# 00_POWER.net
KiCad netlist of a schematic drawn in Altium Designer
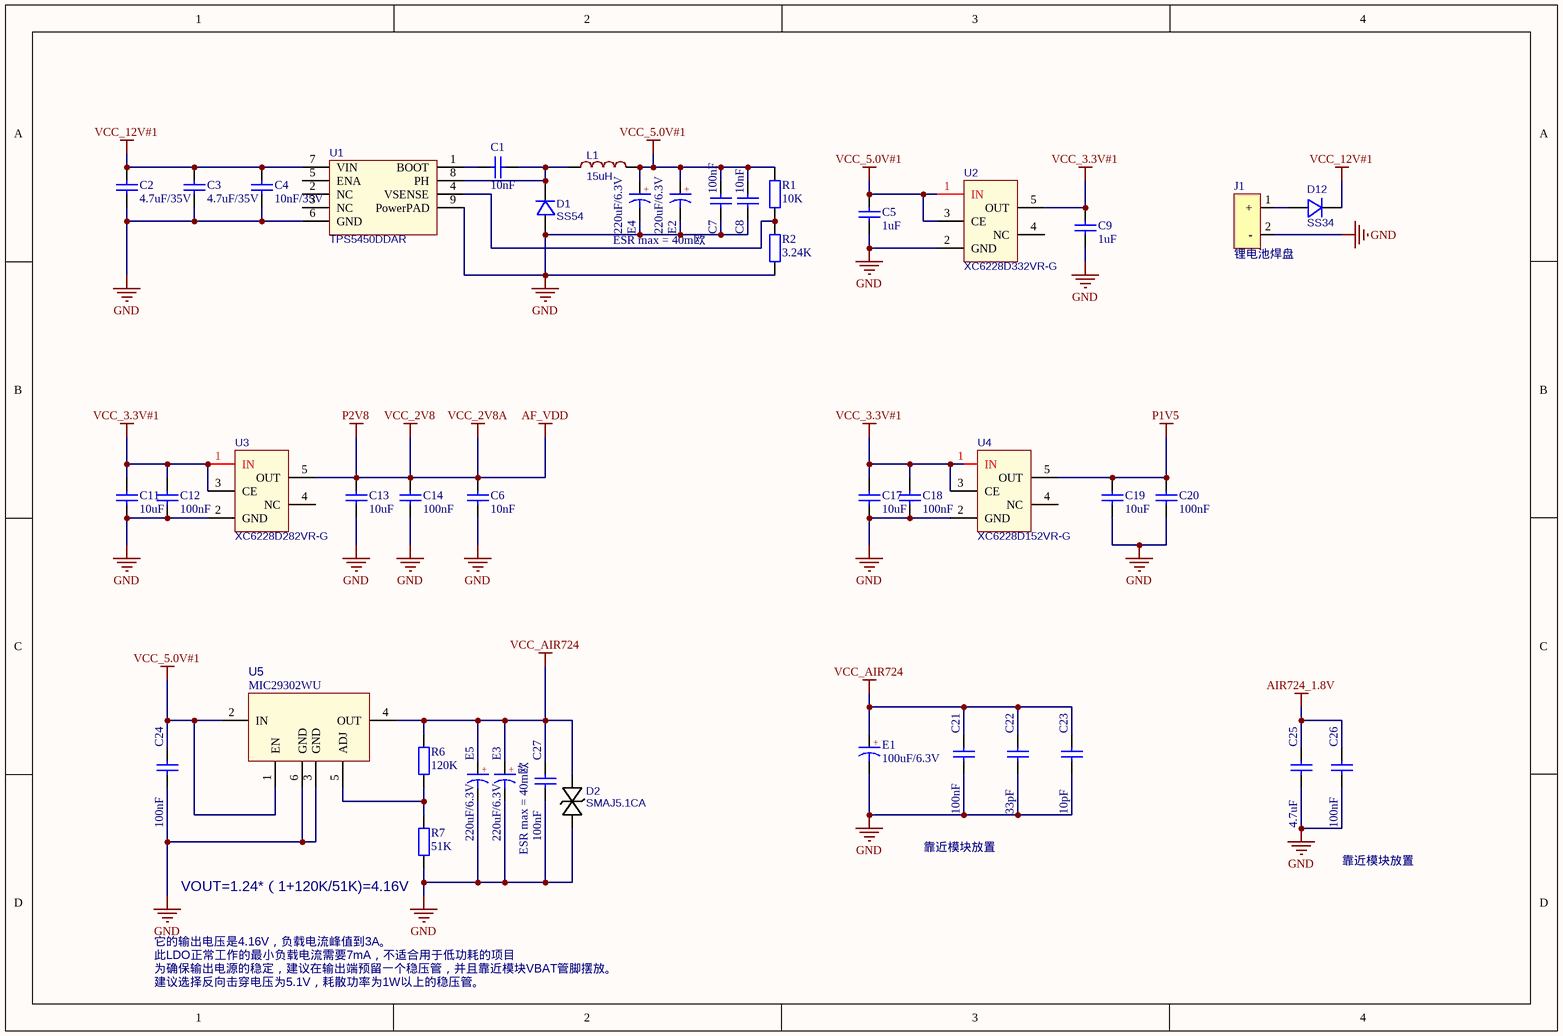
[diagram p0: 00_POWER.SchDoc]

(export (version "E")
  (design (tool "Eeschema 10.0.6"))
  (components
    (comp (ref "C1")
      (value "10nF")
      (footprint "0603-C")
      (description "贴片电容")
      (libsource (lib "封装库") (part "C"))
    )
    (comp (ref "C2")
      (value "4.7uF/35V")
      (footprint "0805-C")
      (description "贴片电容")
      (libsource (lib "封装库") (part "C"))
    )
    (comp (ref "C3")
      (value "4.7uF/35V")
      (footprint "0805-C")
      (description "贴片电容")
      (libsource (lib "封装库") (part "C"))
    )
    (comp (ref "C4")
      (value "10nF/35V")
      (footprint "0603-C")
      (description "贴片电容")
      (libsource (lib "封装库") (part "C"))
    )
    (comp (ref "C5")
      (value "1uF")
      (footprint "0603-C")
      (description "贴片电容")
      (libsource (lib "封装库") (part "C"))
    )
    (comp (ref "C6")
      (value "10nF")
      (footprint "0603-C")
      (description "贴片电容")
      (libsource (lib "封装库") (part "C"))
    )
    (comp (ref "C7")
      (value "100nF")
      (footprint "0603-C")
      (description "贴片电容")
      (libsource (lib "封装库") (part "C"))
    )
    (comp (ref "C8")
      (value "10nF")
      (footprint "0603-C")
      (description "贴片电容")
      (libsource (lib "封装库") (part "C"))
    )
    (comp (ref "C9")
      (value "1uF")
      (footprint "0603-C")
      (description "贴片电容")
      (libsource (lib "封装库") (part "C"))
    )
    (comp (ref "C11")
      (value "10uF")
      (footprint "0603-C")
      (description "贴片电容")
      (libsource (lib "封装库") (part "C"))
    )
    (comp (ref "C12")
      (value "100nF")
      (footprint "0603-C")
      (description "贴片电容")
      (libsource (lib "封装库") (part "C"))
    )
    (comp (ref "C13")
      (value "10uF")
      (footprint "0603-C")
      (description "贴片电容")
      (libsource (lib "封装库") (part "C"))
    )
    (comp (ref "C14")
      (value "100nF")
      (footprint "0603-C")
      (description "贴片电容")
      (libsource (lib "封装库") (part "C"))
    )
    (comp (ref "C17")
      (value "10uF")
      (footprint "0603-C")
      (description "贴片电容")
      (libsource (lib "封装库") (part "C"))
    )
    (comp (ref "C18")
      (value "100nF")
      (footprint "0603-C")
      (description "贴片电容")
      (libsource (lib "封装库") (part "C"))
    )
    (comp (ref "C19")
      (value "10uF")
      (footprint "0603-C")
      (description "贴片电容")
      (libsource (lib "封装库") (part "C"))
    )
    (comp (ref "C20")
      (value "100nF")
      (footprint "0603-C")
      (description "贴片电容")
      (libsource (lib "封装库") (part "C"))
    )
    (comp (ref "C21")
      (value "100nF")
      (footprint "0603-C")
      (description "贴片电容")
      (libsource (lib "封装库") (part "C"))
    )
    (comp (ref "C22")
      (value "33pF")
      (footprint "0603-C")
      (description "贴片电容")
      (libsource (lib "封装库") (part "C"))
    )
    (comp (ref "C23")
      (value "10pF")
      (footprint "0603-C")
      (description "贴片电容")
      (libsource (lib "封装库") (part "C"))
    )
    (comp (ref "C24")
      (value "100nF")
      (footprint "0603-C")
      (description "贴片电容")
      (libsource (lib "封装库") (part "C"))
    )
    (comp (ref "C25")
      (value "4.7uF")
      (footprint "0603-C")
      (description "贴片电容")
      (libsource (lib "封装库") (part "C"))
    )
    (comp (ref "C26")
      (value "100nF")
      (footprint "0603-C")
      (description "贴片电容")
      (libsource (lib "封装库") (part "C"))
    )
    (comp (ref "C27")
      (value "100nF")
      (footprint "0603-C")
      (description "贴片电容")
      (libsource (lib "封装库") (part "C"))
    )
    (comp (ref "D1")
      (value "SS54")
      (footprint "SS34-SMA")
      (fields
        (field (name "BOM_SUPPLIER PART") "C118334")
        (field (name "BOM_MANUFACTURER PART") "D-G060306G1-KS2")
        (field (name "CONTRIBUTOR") "LCSC")
      )
      (libsource (lib "封装库") (part "SS34"))
    )
    (comp (ref "D2")
      (value "SMAJ5.1CA")
      (footprint "ZENER")
      (description "SMAJ6.0CA_C698928")
      (fields
        (field (name "BOM_SUPPLIER PART") "C698928")
        (field (name "BOM_MANUFACTURER PART") "SMAJ6.0CA")
        (field (name "CONTRIBUTOR") "LCSC")
      )
      (libsource (lib "封装库") (part "SMAJ6.0CA"))
    )
    (comp (ref "D12")
      (value "SS34")
      (footprint "SS34-SMA")
      (fields
        (field (name "BOM_SUPPLIER PART") "C118334")
        (field (name "BOM_MANUFACTURER PART") "D-G060306G1-KS2")
        (field (name "CONTRIBUTOR") "LCSC")
      )
      (libsource (lib "封装库") (part "SS34"))
    )
    (comp (ref "E1")
      (value "100uF/6.3V")
      (footprint "CD B(3528)")
      (description "贴片钽电容")
      (libsource (lib "封装库") (part "CT"))
    )
    (comp (ref "E2")
      (value "220uF/6.3V")
      (footprint "CD B(3528)")
      (description "贴片钽电容")
      (libsource (lib "封装库") (part "CT"))
    )
    (comp (ref "E3")
      (value "220uF/6.3V")
      (footprint "CD B(3528)")
      (description "贴片钽电容")
      (libsource (lib "封装库") (part "CT"))
    )
    (comp (ref "E4")
      (value "220uF/6.3V")
      (footprint "CD B(3528)")
      (description "贴片钽电容")
      (libsource (lib "封装库") (part "CT"))
    )
    (comp (ref "E5")
      (value "220uF/6.3V")
      (footprint "CD B(3528)")
      (description "贴片钽电容")
      (libsource (lib "封装库") (part "CT"))
    )
    (comp (ref "J1") (value "锂电池焊盘") (footprint "锂电池焊盘") (libsource (lib "封装库") (part "锂电池焊盘")))
    (comp (ref "L1")
      (value "15uH")
      (footprint "电感7*7*3")
      (description "L")
      (fields
        (field (name "BOM_MANUFACTURER PART") "UPZ2012D800-4R0TF")
        (field (name "BOM_SUPPLIER PART") "C145060")
        (field (name "CONTRIBUTOR") "LCSC")
      )
      (libsource (lib "封装库") (part "L"))
    )
    (comp (ref "R1")
      (value "10K")
      (footprint "0603-R")
      (description "贴片电阻")
      (libsource (lib "封装库") (part "R"))
    )
    (comp (ref "R2")
      (value "3.24K")
      (footprint "0603-R")
      (description "贴片电阻")
      (libsource (lib "封装库") (part "R"))
    )
    (comp (ref "R6")
      (value "120K")
      (footprint "0603-R")
      (description "贴片电阻")
      (libsource (lib "封装库") (part "R"))
    )
    (comp (ref "R7")
      (value "51K")
      (footprint "0603-R")
      (description "贴片电阻")
      (libsource (lib "封装库") (part "R"))
    )
    (comp (ref "U1")
      (value "TPS5450DDAR")
      (footprint "TPS5430")
      (fields (field (name "BOM_MANUFACTURER PART") "TPS5430DDAR") (field (name "BOM_SUPPLIER PART") "C9864"))
      (libsource (lib "封装库") (part "TPS5430DDAR"))
    )
    (comp (ref "U2")
      (value "XC6228D332VR-G")
      (footprint "XC6228D332VR-G")
      (fields (field (name "BOM_SUPPLIER PART") "C69841"))
      (libsource (lib "封装库") (part "XC6228D332VR-G"))
    )
    (comp (ref "U3")
      (value "XC6228D282VR-G")
      (footprint "XC6228D332VR-G")
      (fields
        (field (name "BOM_MANUFACTURER PART") "XC6228D332VR-G")
        (field (name "BOM_SUPPLIER PART") "C69841")
      )
      (libsource (lib "封装库") (part "XC6228D282VR-G"))
    )
    (comp (ref "U4")
      (value "XC6228D152VR-G")
      (footprint "XC6228D332VR-G")
      (fields
        (field (name "BOM_MANUFACTURER PART") "XC6228D332VR-G")
        (field (name "BOM_SUPPLIER PART") "C69841")
      )
      (libsource (lib "封装库") (part "XC6228D282VR-G"))
    )
    (comp (ref "U5")
      (value "MIC29302WU")
      (footprint "MIC29302WU")
      (fields (field (name "MANUFACTURER") "UMW(友台半导体)"))
      (libsource (lib "封装库") (part "MIC29302WU"))
    )
  )
  (nets
    (net (code "1") (name "AF_VDD") (class "Default")
      (node (ref "C13") (pin "2") (pinfunction "2_2") (pintype "passive"))
      (node (ref "C14") (pin "2") (pinfunction "2_2") (pintype "passive"))
      (node (ref "C6") (pin "2") (pinfunction "2_2") (pintype "passive"))
      (node (ref "U3") (pin "5") (pinfunction "OUT_5") (pintype "passive"))
    )
    (net (code "2") (name "AIR724_1.8V") (class "Default")
      (node (ref "C25") (pin "2") (pinfunction "2_2") (pintype "passive"))
      (node (ref "C26") (pin "2") (pinfunction "2_2") (pintype "passive"))
    )
    (net (code "3") (name "GND") (class "Default")
      (node (ref "C11") (pin "1") (pinfunction "1_1") (pintype "passive"))
      (node (ref "C12") (pin "1") (pinfunction "1_1") (pintype "passive"))
      (node (ref "C13") (pin "1") (pinfunction "1_1") (pintype "passive"))
      (node (ref "C14") (pin "1") (pinfunction "1_1") (pintype "passive"))
      (node (ref "C17") (pin "1") (pinfunction "1_1") (pintype "passive"))
      (node (ref "C18") (pin "1") (pinfunction "1_1") (pintype "passive"))
      (node (ref "C19") (pin "1") (pinfunction "1_1") (pintype "passive"))
      (node (ref "C2") (pin "2") (pinfunction "2_2") (pintype "passive"))
      (node (ref "C20") (pin "1") (pinfunction "1_1") (pintype "passive"))
      (node (ref "C21") (pin "1") (pinfunction "1_1") (pintype "passive"))
      (node (ref "C22") (pin "1") (pinfunction "1_1") (pintype "passive"))
      (node (ref "C23") (pin "1") (pinfunction "1_1") (pintype "passive"))
      (node (ref "C24") (pin "1") (pinfunction "1_1") (pintype "passive"))
      (node (ref "C25") (pin "1") (pinfunction "1_1") (pintype "passive"))
      (node (ref "C26") (pin "1") (pinfunction "1_1") (pintype "passive"))
      (node (ref "C27") (pin "1") (pinfunction "1_1") (pintype "passive"))
      (node (ref "C3") (pin "2") (pinfunction "2_2") (pintype "passive"))
      (node (ref "C4") (pin "1") (pinfunction "1_1") (pintype "passive"))
      (node (ref "C5") (pin "1") (pinfunction "1_1") (pintype "passive"))
      (node (ref "C6") (pin "1") (pinfunction "1_1") (pintype "passive"))
      (node (ref "C7") (pin "2") (pinfunction "2_2") (pintype "passive"))
      (node (ref "C8") (pin "2") (pinfunction "2_2") (pintype "passive"))
      (node (ref "C9") (pin "1") (pinfunction "1_1") (pintype "passive"))
      (node (ref "D1") (pin "1") (pinfunction "+_1") (pintype "passive"))
      (node (ref "D2") (pin "2") (pinfunction "A_2") (pintype "passive"))
      (node (ref "E1") (pin "2") (pinfunction "K_2") (pintype "passive"))
      (node (ref "E2") (pin "2") (pinfunction "K_2") (pintype "passive"))
      (node (ref "E3") (pin "2") (pinfunction "K_2") (pintype "passive"))
      (node (ref "E4") (pin "2") (pinfunction "K_2") (pintype "passive"))
      (node (ref "E5") (pin "2") (pinfunction "K_2") (pintype "passive"))
      (node (ref "J1") (pin "2") (pinfunction "-_2") (pintype "passive"))
      (node (ref "R2") (pin "2") (pinfunction "2_2") (pintype "passive"))
      (node (ref "R7") (pin "2") (pinfunction "2_2") (pintype "passive"))
      (node (ref "U1") (pin "6") (pinfunction "GND_6") (pintype "passive"))
      (node (ref "U1") (pin "9") (pinfunction "PowerPAD_9") (pintype "passive"))
      (node (ref "U2") (pin "2") (pinfunction "GND_2") (pintype "passive"))
      (node (ref "U3") (pin "2") (pinfunction "GND_2") (pintype "passive"))
      (node (ref "U4") (pin "2") (pinfunction "GND_2") (pintype "passive"))
      (node (ref "U5") (pin "3") (pinfunction "GND_3") (pintype "passive"))
      (node (ref "U5") (pin "6") (pinfunction "GND_6") (pintype "passive"))
    )
    (net (code "4") (name "Net-(D1--)") (class "Default")
      (node (ref "C1") (pin "1") (pinfunction "1_1") (pintype "passive"))
      (node (ref "D1") (pin "2") (pinfunction "-_2") (pintype "passive"))
      (node (ref "L1") (pin "1") (pinfunction "1_1") (pintype "passive"))
      (node (ref "U1") (pin "8") (pinfunction "PH_8") (pintype "passive"))
    )
    (net (code "5") (name "Net-(D12-+)") (class "Default")
      (node (ref "D12") (pin "1") (pinfunction "+_1") (pintype "passive"))
      (node (ref "J1") (pin "1") (pinfunction "+_1") (pintype "passive"))
    )
    (net (code "6") (name "Net-(U1-BOOT)") (class "Default")
      (node (ref "C1") (pin "2") (pinfunction "2_2") (pintype "passive"))
      (node (ref "U1") (pin "1") (pinfunction "BOOT_1") (pintype "passive"))
    )
    (net (code "7") (name "Net-(U1-VSENSE)") (class "Default")
      (node (ref "R1") (pin "2") (pinfunction "2_2") (pintype "passive"))
      (node (ref "R2") (pin "1") (pinfunction "1_1") (pintype "passive"))
      (node (ref "U1") (pin "4") (pinfunction "VSENSE_4") (pintype "passive"))
    )
    (net (code "8") (name "Net-(U5-ADJ)") (class "Default")
      (node (ref "R6") (pin "2") (pinfunction "2_2") (pintype "passive"))
      (node (ref "R7") (pin "1") (pinfunction "1_1") (pintype "passive"))
      (node (ref "U5") (pin "5") (pinfunction "ADJ_5") (pintype "passive"))
    )
    (net (code "9") (name "P1V5") (class "Default")
      (node (ref "C19") (pin "2") (pinfunction "2_2") (pintype "passive"))
      (node (ref "C20") (pin "2") (pinfunction "2_2") (pintype "passive"))
      (node (ref "U4") (pin "5") (pinfunction "OUT_5") (pintype "passive"))
    )
    (net (code "10") (name "VCC_3.3V#1") (class "Default")
      (node (ref "C11") (pin "2") (pinfunction "2_2") (pintype "passive"))
      (node (ref "C12") (pin "2") (pinfunction "2_2") (pintype "passive"))
      (node (ref "C17") (pin "2") (pinfunction "2_2") (pintype "passive"))
      (node (ref "C18") (pin "2") (pinfunction "2_2") (pintype "passive"))
      (node (ref "C9") (pin "2") (pinfunction "2_2") (pintype "passive"))
      (node (ref "U2") (pin "5") (pinfunction "OUT_5") (pintype "passive"))
      (node (ref "U3") (pin "1") (pinfunction "IN_1") (pintype "passive"))
      (node (ref "U3") (pin "3") (pinfunction "CE_3") (pintype "passive"))
      (node (ref "U4") (pin "1") (pinfunction "IN_1") (pintype "passive"))
      (node (ref "U4") (pin "3") (pinfunction "CE_3") (pintype "passive"))
    )
    (net (code "11") (name "VCC_5.0V#1") (class "Default")
      (node (ref "C24") (pin "2") (pinfunction "2_2") (pintype "passive"))
      (node (ref "C5") (pin "2") (pinfunction "2_2") (pintype "passive"))
      (node (ref "C7") (pin "1") (pinfunction "1_1") (pintype "passive"))
      (node (ref "C8") (pin "1") (pinfunction "1_1") (pintype "passive"))
      (node (ref "E2") (pin "1") (pinfunction "A_1") (pintype "passive"))
      (node (ref "E4") (pin "1") (pinfunction "A_1") (pintype "passive"))
      (node (ref "L1") (pin "2") (pinfunction "2_2") (pintype "passive"))
      (node (ref "R1") (pin "1") (pinfunction "1_1") (pintype "passive"))
      (node (ref "U2") (pin "1") (pinfunction "IN_1") (pintype "passive"))
      (node (ref "U2") (pin "3") (pinfunction "CE_3") (pintype "passive"))
      (node (ref "U5") (pin "1") (pinfunction "EN_1") (pintype "passive"))
      (node (ref "U5") (pin "2") (pinfunction "IN_2") (pintype "passive"))
    )
    (net (code "12") (name "VCC_12V#1") (class "Default")
      (node (ref "C2") (pin "1") (pinfunction "1_1") (pintype "passive"))
      (node (ref "C3") (pin "1") (pinfunction "1_1") (pintype "passive"))
      (node (ref "C4") (pin "2") (pinfunction "2_2") (pintype "passive"))
      (node (ref "D12") (pin "2") (pinfunction "-_2") (pintype "passive"))
      (node (ref "U1") (pin "7") (pinfunction "VIN_7") (pintype "passive"))
    )
    (net (code "13") (name "VCC_AIR724") (class "Default")
      (node (ref "C21") (pin "2") (pinfunction "2_2") (pintype "passive"))
      (node (ref "C22") (pin "2") (pinfunction "2_2") (pintype "passive"))
      (node (ref "C23") (pin "2") (pinfunction "2_2") (pintype "passive"))
      (node (ref "C27") (pin "2") (pinfunction "2_2") (pintype "passive"))
      (node (ref "D2") (pin "1") (pinfunction "C_1") (pintype "passive"))
      (node (ref "E1") (pin "1") (pinfunction "A_1") (pintype "passive"))
      (node (ref "E3") (pin "1") (pinfunction "A_1") (pintype "passive"))
      (node (ref "E5") (pin "1") (pinfunction "A_1") (pintype "passive"))
      (node (ref "R6") (pin "1") (pinfunction "1_1") (pintype "passive"))
      (node (ref "U5") (pin "4") (pinfunction "OUT_4") (pintype "passive"))
    )
    (net (code "14") (name "unconnected-(U1-ENA-Pad5)") (class "Default")
      (node (ref "U1") (pin "5") (pinfunction "ENA_5") (pintype "passive"))
    )
    (net (code "15") (name "unconnected-(U1-NC-Pad2)") (class "Default")
      (node (ref "U1") (pin "2") (pinfunction "NC_2") (pintype "passive"))
    )
    (net (code "16") (name "unconnected-(U1-NC-Pad3)") (class "Default")
      (node (ref "U1") (pin "3") (pinfunction "NC_3") (pintype "passive"))
    )
    (net (code "17") (name "unconnected-(U2-NC-Pad4)") (class "Default")
      (node (ref "U2") (pin "4") (pinfunction "NC_4") (pintype "passive"))
    )
    (net (code "18") (name "unconnected-(U3-NC-Pad4)") (class "Default")
      (node (ref "U3") (pin "4") (pinfunction "NC_4") (pintype "passive"))
    )
    (net (code "19") (name "unconnected-(U4-NC-Pad4)") (class "Default")
      (node (ref "U4") (pin "4") (pinfunction "NC_4") (pintype "passive"))
    )
  )
)
